# bottom.net
KiCad netlist of a schematic drawn in EAGLE
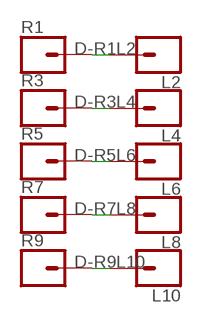
[diagram p0: schematic, sheet 1]

(export (version "E")
  (design (tool "Eeschema 10.0.6"))
  (components
    (comp (ref "L2")
      (value "CONN_01")
      (footprint "eagle-import:1X01")
      (libsource (lib "eagle-import") (part "CONN_01"))
    )
    (comp (ref "L4")
      (value "CONN_01")
      (footprint "eagle-import:1X01")
      (libsource (lib "eagle-import") (part "CONN_01"))
    )
    (comp (ref "L6")
      (value "CONN_01")
      (footprint "eagle-import:1X01")
      (libsource (lib "eagle-import") (part "CONN_01"))
    )
    (comp (ref "L8")
      (value "CONN_01")
      (footprint "eagle-import:1X01")
      (libsource (lib "eagle-import") (part "CONN_01"))
    )
    (comp (ref "L10")
      (value "CONN_01")
      (footprint "eagle-import:1X01")
      (libsource (lib "eagle-import") (part "CONN_01"))
    )
    (comp (ref "R1")
      (value "CONN_01")
      (footprint "eagle-import:1X01")
      (libsource (lib "eagle-import") (part "CONN_01"))
    )
    (comp (ref "R3")
      (value "CONN_01")
      (footprint "eagle-import:1X01")
      (libsource (lib "eagle-import") (part "CONN_01"))
    )
    (comp (ref "R5")
      (value "CONN_01")
      (footprint "eagle-import:1X01")
      (libsource (lib "eagle-import") (part "CONN_01"))
    )
    (comp (ref "R7")
      (value "CONN_01")
      (footprint "eagle-import:1X01")
      (libsource (lib "eagle-import") (part "CONN_01"))
    )
    (comp (ref "R9")
      (value "CONN_01")
      (footprint "eagle-import:1X01")
      (libsource (lib "eagle-import") (part "CONN_01"))
    )
  )
  (nets
    (net (code "1") (name "/D-R1L2") (class "Default")
      (node (ref "L2") (pin "1") (pinfunction "1_1") (pintype "passive"))
      (node (ref "R1") (pin "1") (pinfunction "1_1") (pintype "passive"))
    )
    (net (code "2") (name "/D-R3L4") (class "Default")
      (node (ref "L4") (pin "1") (pinfunction "1_1") (pintype "passive"))
      (node (ref "R3") (pin "1") (pinfunction "1_1") (pintype "passive"))
    )
    (net (code "3") (name "/D-R5L6") (class "Default")
      (node (ref "L6") (pin "1") (pinfunction "1_1") (pintype "passive"))
      (node (ref "R5") (pin "1") (pinfunction "1_1") (pintype "passive"))
    )
    (net (code "4") (name "/D-R7L8") (class "Default")
      (node (ref "L8") (pin "1") (pinfunction "1_1") (pintype "passive"))
      (node (ref "R7") (pin "1") (pinfunction "1_1") (pintype "passive"))
    )
    (net (code "5") (name "/D-R9L10") (class "Default")
      (node (ref "L10") (pin "1") (pinfunction "1_1") (pintype "passive"))
      (node (ref "R9") (pin "1") (pinfunction "1_1") (pintype "passive"))
    )
  )
)
